# rita_milton_civ.net
KiCad netlist of a schematic drawn in EAGLE
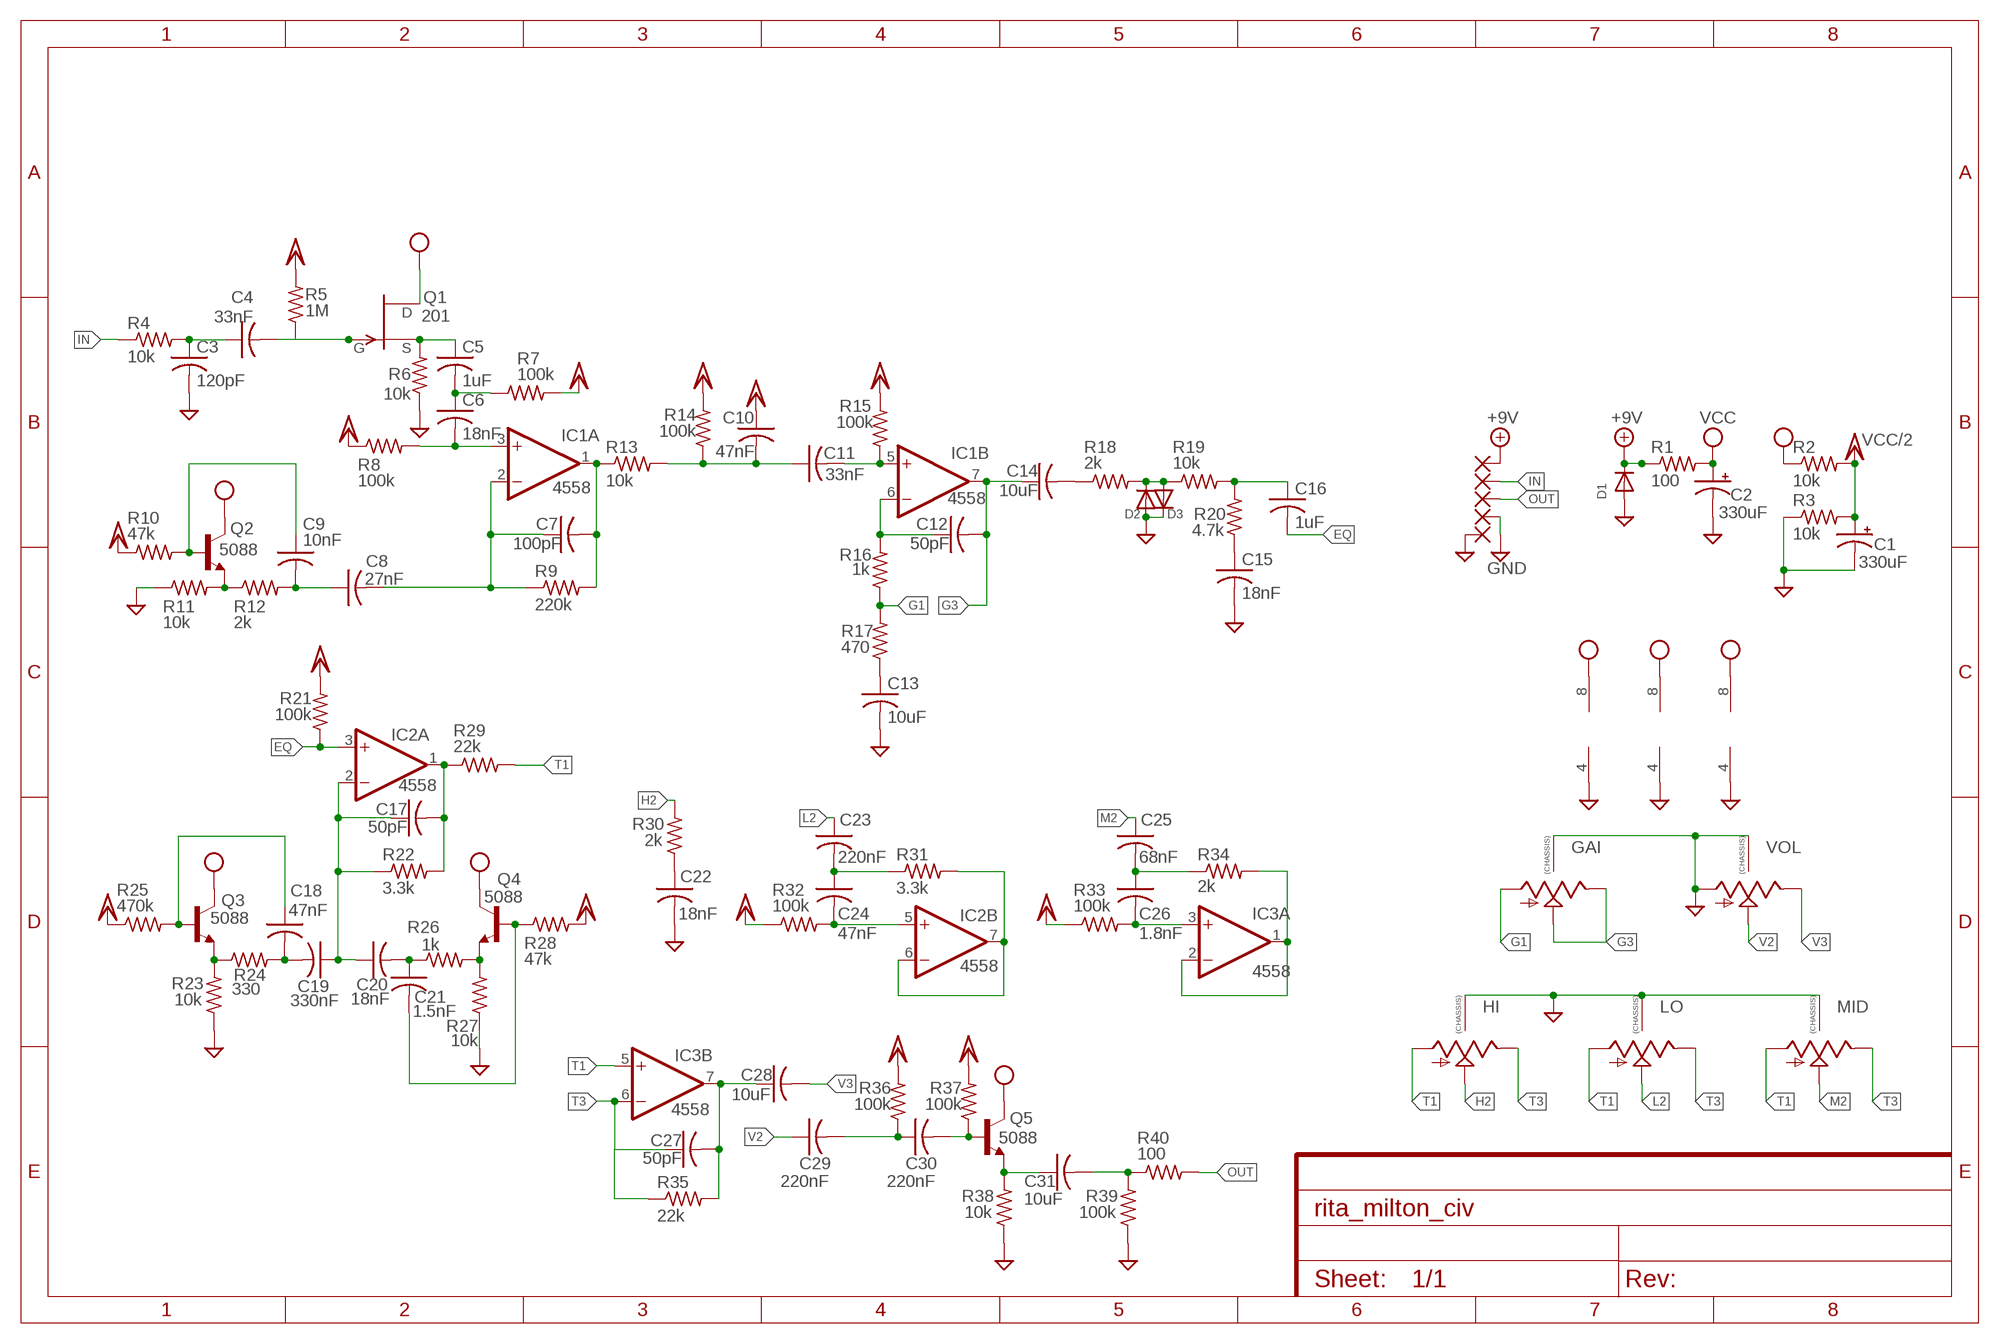
[diagram p0: schematic, sheet 1]

(export (version "E")
  (design (tool "Eeschema 10.0.6"))
  (components
    (comp (ref "C1")
      (value "330uF")
      (footprint "eagle-import:080_035")
      (libsource (lib "eagle-import") (part "0801"))
    )
    (comp (ref "C2")
      (value "330uF")
      (footprint "eagle-import:080_035")
      (libsource (lib "eagle-import") (part "0801"))
    )
    (comp (ref "C3")
      (value "120pF")
      (footprint "eagle-import:C0603")
      (libsource (lib "eagle-import") (part "adafruit_420_C-USC0603"))
    )
    (comp (ref "C4")
      (value "33nF")
      (footprint "eagle-import:C0603")
      (libsource (lib "eagle-import") (part "adafruit_420_C-USC0603"))
    )
    (comp (ref "C5")
      (value "1uF")
      (footprint "eagle-import:C0805")
      (libsource (lib "eagle-import") (part "adafruit_420_C-USC0805"))
    )
    (comp (ref "C6")
      (value "18nF")
      (footprint "eagle-import:C0603")
      (libsource (lib "eagle-import") (part "adafruit_420_C-USC0603"))
    )
    (comp (ref "C7")
      (value "100pF")
      (footprint "eagle-import:C0603")
      (libsource (lib "eagle-import") (part "adafruit_420_C-USC0603"))
    )
    (comp (ref "C8")
      (value "27nF")
      (footprint "eagle-import:C0603")
      (libsource (lib "eagle-import") (part "adafruit_420_C-USC0603"))
    )
    (comp (ref "C9")
      (value "10nF")
      (footprint "eagle-import:C0603")
      (libsource (lib "eagle-import") (part "adafruit_420_C-USC0603"))
    )
    (comp (ref "C10")
      (value "47nF")
      (footprint "eagle-import:C0603")
      (libsource (lib "eagle-import") (part "adafruit_420_C-USC0603"))
    )
    (comp (ref "C11")
      (value "33nF")
      (footprint "eagle-import:C0603")
      (libsource (lib "eagle-import") (part "adafruit_420_C-USC0603"))
    )
    (comp (ref "C12")
      (value "50pF")
      (footprint "eagle-import:C0603")
      (libsource (lib "eagle-import") (part "adafruit_420_C-USC0603"))
    )
    (comp (ref "C13")
      (value "10uF")
      (footprint "eagle-import:C1206")
      (libsource (lib "eagle-import") (part "C-USC1206"))
    )
    (comp (ref "C14")
      (value "10uF")
      (footprint "eagle-import:C1206")
      (libsource (lib "eagle-import") (part "C-USC1206"))
    )
    (comp (ref "C15")
      (value "18nF")
      (footprint "eagle-import:C0603")
      (libsource (lib "eagle-import") (part "adafruit_420_C-USC0603"))
    )
    (comp (ref "C16")
      (value "1uF")
      (footprint "eagle-import:C0805")
      (libsource (lib "eagle-import") (part "adafruit_420_C-USC0805"))
    )
    (comp (ref "C17")
      (value "50pF")
      (footprint "eagle-import:C0603")
      (libsource (lib "eagle-import") (part "adafruit_420_C-USC0603"))
    )
    (comp (ref "C18")
      (value "47nF")
      (footprint "eagle-import:C0603")
      (libsource (lib "eagle-import") (part "adafruit_420_C-USC0603"))
    )
    (comp (ref "C19")
      (value "330nF")
      (footprint "eagle-import:C0603")
      (libsource (lib "eagle-import") (part "adafruit_420_C-USC0603"))
    )
    (comp (ref "C20")
      (value "18nF")
      (footprint "eagle-import:C0603")
      (libsource (lib "eagle-import") (part "adafruit_420_C-USC0603"))
    )
    (comp (ref "C21")
      (value "1.5nF")
      (footprint "eagle-import:C0603")
      (libsource (lib "eagle-import") (part "adafruit_420_C-USC0603"))
    )
    (comp (ref "C22")
      (value "18nF")
      (footprint "eagle-import:C0603")
      (libsource (lib "eagle-import") (part "adafruit_420_C-USC0603"))
    )
    (comp (ref "C23")
      (value "220nF")
      (footprint "eagle-import:C0603")
      (libsource (lib "eagle-import") (part "adafruit_420_C-USC0603"))
    )
    (comp (ref "C24")
      (value "47nF")
      (footprint "eagle-import:C0603")
      (libsource (lib "eagle-import") (part "adafruit_420_C-USC0603"))
    )
    (comp (ref "C25")
      (value "68nF")
      (footprint "eagle-import:C0603")
      (libsource (lib "eagle-import") (part "adafruit_420_C-USC0603"))
    )
    (comp (ref "C26")
      (value "1.8nF")
      (footprint "eagle-import:C0603")
      (libsource (lib "eagle-import") (part "adafruit_420_C-USC0603"))
    )
    (comp (ref "C27")
      (value "50pF")
      (footprint "eagle-import:C0603")
      (libsource (lib "eagle-import") (part "adafruit_420_C-USC0603"))
    )
    (comp (ref "C28")
      (value "10uF")
      (footprint "eagle-import:C1206")
      (libsource (lib "eagle-import") (part "C-USC1206"))
    )
    (comp (ref "C29")
      (value "220nF")
      (footprint "eagle-import:C0603")
      (libsource (lib "eagle-import") (part "adafruit_420_C-USC0603"))
    )
    (comp (ref "C30")
      (value "220nF")
      (footprint "eagle-import:C0603")
      (libsource (lib "eagle-import") (part "adafruit_420_C-USC0603"))
    )
    (comp (ref "C31")
      (value "10uF")
      (footprint "eagle-import:C1206")
      (libsource (lib "eagle-import") (part "C-USC1206"))
    )
    (comp (ref "D1")
      (value "DIODESOD-123")
      (footprint "eagle-import:SOD-123")
      (libsource (lib "eagle-import") (part "DIODESOD-123"))
    )
    (comp (ref "D2")
      (value "DIODESOD-123")
      (footprint "eagle-import:SOD-123")
      (libsource (lib "eagle-import") (part "DIODESOD-123"))
    )
    (comp (ref "D3")
      (value "DIODESOD-123")
      (footprint "eagle-import:SOD-123")
      (libsource (lib "eagle-import") (part "DIODESOD-123"))
    )
    (comp (ref "GAI")
      (value "9MM_SNAP-IN_POT_CHASSIS")
      (footprint "eagle-import:9MM_SNAP-IN_POT")
      (libsource (lib "eagle-import") (part "9MM_SNAP-IN_POT_CHASSIS"))
    )
    (comp (ref "HI")
      (value "9MM_SNAP-IN_POT_CHASSIS")
      (footprint "eagle-import:9MM_SNAP-IN_POT")
      (libsource (lib "eagle-import") (part "9MM_SNAP-IN_POT_CHASSIS"))
    )
    (comp (ref "IC1")
      (value "4558")
      (footprint "eagle-import:SO08")
      (libsource (lib "eagle-import") (part "4558DLM"))
    )
    (comp (ref "IC2")
      (value "4558")
      (footprint "eagle-import:SO08")
      (libsource (lib "eagle-import") (part "4558DLM"))
    )
    (comp (ref "IC3")
      (value "4558")
      (footprint "eagle-import:SO08")
      (libsource (lib "eagle-import") (part "4558DLM"))
    )
    (comp (ref "LO")
      (value "9MM_SNAP-IN_POT_CHASSIS")
      (footprint "eagle-import:9MM_SNAP-IN_POT")
      (libsource (lib "eagle-import") (part "9MM_SNAP-IN_POT_CHASSIS"))
    )
    (comp (ref "MID")
      (value "9MM_SNAP-IN_POT_CHASSIS")
      (footprint "eagle-import:9MM_SNAP-IN_POT")
      (libsource (lib "eagle-import") (part "9MM_SNAP-IN_POT_CHASSIS"))
    )
    (comp (ref "PAD1")
      (value "1,6/0,8")
      (footprint "eagle-import:1,6_0,8")
      (libsource (lib "eagle-import") (part "1,6/0,8"))
    )
    (comp (ref "PAD2")
      (value "1,6/0,8")
      (footprint "eagle-import:1,6_0,8")
      (libsource (lib "eagle-import") (part "1,6/0,8"))
    )
    (comp (ref "PAD3")
      (value "1,6/0,8")
      (footprint "eagle-import:1,6_0,8")
      (libsource (lib "eagle-import") (part "1,6/0,8"))
    )
    (comp (ref "PAD4")
      (value "1,6/0,8")
      (footprint "eagle-import:1,6_0,8")
      (libsource (lib "eagle-import") (part "1,6/0,8"))
    )
    (comp (ref "PAD5")
      (value "1,6/0,8")
      (footprint "eagle-import:1,6_0,8")
      (libsource (lib "eagle-import") (part "1,6/0,8"))
    )
    (comp (ref "Q1")
      (value "201")
      (footprint "eagle-import:SOT23")
      (libsource (lib "eagle-import") (part "?20SST1"))
    )
    (comp (ref "Q2")
      (value "5088")
      (footprint "eagle-import:SOT23")
      (libsource (lib "eagle-import") (part "TRANSISTOR_NPNMMBT5088"))
    )
    (comp (ref "Q3")
      (value "5088")
      (footprint "eagle-import:SOT23")
      (libsource (lib "eagle-import") (part "TRANSISTOR_NPNMMBT5088"))
    )
    (comp (ref "Q4")
      (value "5088")
      (footprint "eagle-import:SOT23")
      (libsource (lib "eagle-import") (part "TRANSISTOR_NPNMMBT5088"))
    )
    (comp (ref "Q5")
      (value "5088")
      (footprint "eagle-import:SOT23")
      (libsource (lib "eagle-import") (part "TRANSISTOR_NPNMMBT5088"))
    )
    (comp (ref "R1")
      (value "100")
      (footprint "eagle-import:R0805")
      (libsource (lib "eagle-import") (part "R-US_R0805"))
    )
    (comp (ref "R2")
      (value "10k")
      (footprint "eagle-import:R0603")
      (libsource (lib "eagle-import") (part "R-US_R0603"))
    )
    (comp (ref "R3")
      (value "10k")
      (footprint "eagle-import:R0603")
      (libsource (lib "eagle-import") (part "R-US_R0603"))
    )
    (comp (ref "R4")
      (value "10k")
      (footprint "eagle-import:R0603")
      (libsource (lib "eagle-import") (part "adafruit_420_R-US_R0603"))
    )
    (comp (ref "R5")
      (value "1M")
      (footprint "eagle-import:R0603")
      (libsource (lib "eagle-import") (part "adafruit_420_R-US_R0603"))
    )
    (comp (ref "R6")
      (value "10k")
      (footprint "eagle-import:R0603")
      (libsource (lib "eagle-import") (part "adafruit_420_R-US_R0603"))
    )
    (comp (ref "R7")
      (value "100k")
      (footprint "eagle-import:R0603")
      (libsource (lib "eagle-import") (part "adafruit_420_R-US_R0603"))
    )
    (comp (ref "R8")
      (value "100k")
      (footprint "eagle-import:R0603")
      (libsource (lib "eagle-import") (part "adafruit_420_R-US_R0603"))
    )
    (comp (ref "R9")
      (value "220k")
      (footprint "eagle-import:R0603")
      (libsource (lib "eagle-import") (part "adafruit_420_R-US_R0603"))
    )
    (comp (ref "R10")
      (value "47k")
      (footprint "eagle-import:R0603")
      (libsource (lib "eagle-import") (part "adafruit_420_R-US_R0603"))
    )
    (comp (ref "R11")
      (value "10k")
      (footprint "eagle-import:R0603")
      (libsource (lib "eagle-import") (part "adafruit_420_R-US_R0603"))
    )
    (comp (ref "R12")
      (value "2k")
      (footprint "eagle-import:R0603")
      (libsource (lib "eagle-import") (part "adafruit_420_R-US_R0603"))
    )
    (comp (ref "R13")
      (value "10k")
      (footprint "eagle-import:R0603")
      (libsource (lib "eagle-import") (part "adafruit_420_R-US_R0603"))
    )
    (comp (ref "R14")
      (value "100k")
      (footprint "eagle-import:R0603")
      (libsource (lib "eagle-import") (part "adafruit_420_R-US_R0603"))
    )
    (comp (ref "R15")
      (value "100k")
      (footprint "eagle-import:R0603")
      (libsource (lib "eagle-import") (part "adafruit_420_R-US_R0603"))
    )
    (comp (ref "R16")
      (value "1k")
      (footprint "eagle-import:R0603")
      (libsource (lib "eagle-import") (part "adafruit_420_R-US_R0603"))
    )
    (comp (ref "R17")
      (value "470")
      (footprint "eagle-import:R0603")
      (libsource (lib "eagle-import") (part "adafruit_420_R-US_R0603"))
    )
    (comp (ref "R18")
      (value "2k")
      (footprint "eagle-import:R0603")
      (libsource (lib "eagle-import") (part "adafruit_420_R-US_R0603"))
    )
    (comp (ref "R19")
      (value "10k")
      (footprint "eagle-import:R0603")
      (libsource (lib "eagle-import") (part "adafruit_420_R-US_R0603"))
    )
    (comp (ref "R20")
      (value "4.7k")
      (footprint "eagle-import:R0603")
      (libsource (lib "eagle-import") (part "adafruit_420_R-US_R0603"))
    )
    (comp (ref "R21")
      (value "100k")
      (footprint "eagle-import:R0603")
      (libsource (lib "eagle-import") (part "adafruit_420_R-US_R0603"))
    )
    (comp (ref "R22")
      (value "3.3k")
      (footprint "eagle-import:R0603")
      (libsource (lib "eagle-import") (part "adafruit_420_R-US_R0603"))
    )
    (comp (ref "R23")
      (value "10k")
      (footprint "eagle-import:R0603")
      (libsource (lib "eagle-import") (part "adafruit_420_R-US_R0603"))
    )
    (comp (ref "R24")
      (value "330")
      (footprint "eagle-import:R0603")
      (libsource (lib "eagle-import") (part "adafruit_420_R-US_R0603"))
    )
    (comp (ref "R25")
      (value "470k")
      (footprint "eagle-import:R0603")
      (libsource (lib "eagle-import") (part "adafruit_420_R-US_R0603"))
    )
    (comp (ref "R26")
      (value "1k")
      (footprint "eagle-import:R0603")
      (libsource (lib "eagle-import") (part "adafruit_420_R-US_R0603"))
    )
    (comp (ref "R27")
      (value "10k")
      (footprint "eagle-import:R0603")
      (libsource (lib "eagle-import") (part "adafruit_420_R-US_R0603"))
    )
    (comp (ref "R28")
      (value "47k")
      (footprint "eagle-import:R0603")
      (libsource (lib "eagle-import") (part "adafruit_420_R-US_R0603"))
    )
    (comp (ref "R29")
      (value "22k")
      (footprint "eagle-import:R0603")
      (libsource (lib "eagle-import") (part "adafruit_420_R-US_R0603"))
    )
    (comp (ref "R30")
      (value "2k")
      (footprint "eagle-import:R0603")
      (libsource (lib "eagle-import") (part "adafruit_420_R-US_R0603"))
    )
    (comp (ref "R31")
      (value "3.3k")
      (footprint "eagle-import:R0603")
      (libsource (lib "eagle-import") (part "adafruit_420_R-US_R0603"))
    )
    (comp (ref "R32")
      (value "100k")
      (footprint "eagle-import:R0603")
      (libsource (lib "eagle-import") (part "adafruit_420_R-US_R0603"))
    )
    (comp (ref "R33")
      (value "100k")
      (footprint "eagle-import:R0603")
      (libsource (lib "eagle-import") (part "adafruit_420_R-US_R0603"))
    )
    (comp (ref "R34")
      (value "2k")
      (footprint "eagle-import:R0603")
      (libsource (lib "eagle-import") (part "adafruit_420_R-US_R0603"))
    )
    (comp (ref "R35")
      (value "22k")
      (footprint "eagle-import:R0603")
      (libsource (lib "eagle-import") (part "R-US_R0603"))
    )
    (comp (ref "R36")
      (value "100k")
      (footprint "eagle-import:R0603")
      (libsource (lib "eagle-import") (part "adafruit_420_R-US_R0603"))
    )
    (comp (ref "R37")
      (value "100k")
      (footprint "eagle-import:R0603")
      (libsource (lib "eagle-import") (part "adafruit_420_R-US_R0603"))
    )
    (comp (ref "R38")
      (value "10k")
      (footprint "eagle-import:R0603")
      (libsource (lib "eagle-import") (part "adafruit_420_R-US_R0603"))
    )
    (comp (ref "R39")
      (value "100k")
      (footprint "eagle-import:R0603")
      (libsource (lib "eagle-import") (part "adafruit_420_R-US_R0603"))
    )
    (comp (ref "R40")
      (value "100")
      (footprint "eagle-import:R0603")
      (libsource (lib "eagle-import") (part "adafruit_420_R-US_R0603"))
    )
    (comp (ref "VOL")
      (value "9MM_SNAP-IN_POT_CHASSIS")
      (footprint "eagle-import:9MM_SNAP-IN_POT")
      (libsource (lib "eagle-import") (part "9MM_SNAP-IN_POT_CHASSIS"))
    )
  )
  (nets
    (net (code "1") (name "+9V") (class "Default")
      (node (ref "D1") (pin "C") (pinfunction "C_C") (pintype "passive"))
      (node (ref "PAD1") (pin "1") (pinfunction "P_1") (pintype "passive"))
      (node (ref "R1") (pin "1") (pinfunction "1_1") (pintype "passive"))
    )
    (net (code "2") (name "EQ") (class "Default")
      (node (ref "C16") (pin "2") (pinfunction "2_2") (pintype "passive"))
      (node (ref "IC2") (pin "3") (pinfunction "+IN_3") (pintype "input"))
      (node (ref "R21") (pin "1") (pinfunction "1_1") (pintype "passive"))
    )
    (net (code "3") (name "G1") (class "Default")
      (node (ref "GAI") (pin "1") (pinfunction "A_1") (pintype "passive"))
      (node (ref "R16") (pin "1") (pinfunction "1_1") (pintype "passive"))
      (node (ref "R17") (pin "2") (pinfunction "2_2") (pintype "passive"))
    )
    (net (code "4") (name "G3") (class "Default")
      (node (ref "C12") (pin "2") (pinfunction "2_2") (pintype "passive"))
      (node (ref "C14") (pin "1") (pinfunction "1_1") (pintype "passive"))
      (node (ref "GAI") (pin "2") (pinfunction "S_2") (pintype "passive"))
      (node (ref "GAI") (pin "3") (pinfunction "E_3") (pintype "passive"))
      (node (ref "IC1") (pin "7") (pinfunction "OUT_7") (pintype "output"))
    )
    (net (code "5") (name "GND") (class "Default")
      (node (ref "C1") (pin "-") (pinfunction "-_-") (pintype "passive"))
      (node (ref "C13") (pin "2") (pinfunction "2_2") (pintype "passive"))
      (node (ref "C15") (pin "2") (pinfunction "2_2") (pintype "passive"))
      (node (ref "C2") (pin "-") (pinfunction "-_-") (pintype "passive"))
      (node (ref "C22") (pin "2") (pinfunction "2_2") (pintype "passive"))
      (node (ref "C3") (pin "2") (pinfunction "2_2") (pintype "passive"))
      (node (ref "D1") (pin "A") (pinfunction "A_A") (pintype "passive"))
      (node (ref "D2") (pin "A") (pinfunction "A_A") (pintype "passive"))
      (node (ref "D3") (pin "C") (pinfunction "C_C") (pintype "passive"))
      (node (ref "GAI") (pin "CHASSIS1") (pinfunction "P$1_CHASSIS1") (pintype "passive"))
      (node (ref "GAI") (pin "CHASSIS2") (pinfunction "P$1_CHASSIS2") (pintype "passive"))
      (node (ref "HI") (pin "CHASSIS1") (pinfunction "P$1_CHASSIS1") (pintype "passive"))
      (node (ref "HI") (pin "CHASSIS2") (pinfunction "P$1_CHASSIS2") (pintype "passive"))
      (node (ref "IC1") (pin "4") (pinfunction "V-_4") (pintype "power_in"))
      (node (ref "IC2") (pin "4") (pinfunction "V-_4") (pintype "power_in"))
      (node (ref "IC3") (pin "4") (pinfunction "V-_4") (pintype "power_in"))
      (node (ref "LO") (pin "CHASSIS1") (pinfunction "P$1_CHASSIS1") (pintype "passive"))
      (node (ref "LO") (pin "CHASSIS2") (pinfunction "P$1_CHASSIS2") (pintype "passive"))
      (node (ref "MID") (pin "CHASSIS1") (pinfunction "P$1_CHASSIS1") (pintype "passive"))
      (node (ref "MID") (pin "CHASSIS2") (pinfunction "P$1_CHASSIS2") (pintype "passive"))
      (node (ref "PAD4") (pin "1") (pinfunction "P_1") (pintype "passive"))
      (node (ref "PAD5") (pin "1") (pinfunction "P_1") (pintype "passive"))
      (node (ref "R11") (pin "1") (pinfunction "1_1") (pintype "passive"))
      (node (ref "R23") (pin "1") (pinfunction "1_1") (pintype "passive"))
      (node (ref "R27") (pin "1") (pinfunction "1_1") (pintype "passive"))
      (node (ref "R3") (pin "1") (pinfunction "1_1") (pintype "passive"))
      (node (ref "R38") (pin "1") (pinfunction "1_1") (pintype "passive"))
      (node (ref "R39") (pin "1") (pinfunction "1_1") (pintype "passive"))
      (node (ref "R6") (pin "1") (pinfunction "1_1") (pintype "passive"))
      (node (ref "VOL") (pin "1") (pinfunction "A_1") (pintype "passive"))
      (node (ref "VOL") (pin "CHASSIS1") (pinfunction "P$1_CHASSIS1") (pintype "passive"))
      (node (ref "VOL") (pin "CHASSIS2") (pinfunction "P$1_CHASSIS2") (pintype "passive"))
    )
    (net (code "6") (name "H2") (class "Default")
      (node (ref "HI") (pin "2") (pinfunction "S_2") (pintype "passive"))
      (node (ref "R30") (pin "2") (pinfunction "2_2") (pintype "passive"))
    )
    (net (code "7") (name "IN") (class "Default")
      (node (ref "PAD2") (pin "1") (pinfunction "P_1") (pintype "passive"))
      (node (ref "R4") (pin "1") (pinfunction "1_1") (pintype "passive"))
    )
    (net (code "8") (name "L2") (class "Default")
      (node (ref "C23") (pin "1") (pinfunction "1_1") (pintype "passive"))
      (node (ref "LO") (pin "2") (pinfunction "S_2") (pintype "passive"))
    )
    (net (code "9") (name "M2") (class "Default")
      (node (ref "C25") (pin "1") (pinfunction "1_1") (pintype "passive"))
      (node (ref "MID") (pin "2") (pinfunction "S_2") (pintype "passive"))
    )
    (net (code "10") (name "Net-(C3-Pad1)") (class "Default")
      (node (ref "C3") (pin "1") (pinfunction "1_1") (pintype "passive"))
      (node (ref "C4") (pin "1") (pinfunction "1_1") (pintype "passive"))
      (node (ref "R4") (pin "2") (pinfunction "2_2") (pintype "passive"))
    )
    (net (code "11") (name "Net-(C5-Pad2)") (class "Default")
      (node (ref "C5") (pin "2") (pinfunction "2_2") (pintype "passive"))
      (node (ref "C6") (pin "1") (pinfunction "1_1") (pintype "passive"))
      (node (ref "R7") (pin "1") (pinfunction "1_1") (pintype "passive"))
    )
    (net (code "12") (name "Net-(C8-Pad1)") (class "Default")
      (node (ref "C8") (pin "1") (pinfunction "1_1") (pintype "passive"))
      (node (ref "C9") (pin "2") (pinfunction "2_2") (pintype "passive"))
      (node (ref "R12") (pin "2") (pinfunction "2_2") (pintype "passive"))
    )
    (net (code "13") (name "Net-(C10-Pad2)") (class "Default")
      (node (ref "C10") (pin "2") (pinfunction "2_2") (pintype "passive"))
      (node (ref "C11") (pin "1") (pinfunction "1_1") (pintype "passive"))
      (node (ref "R13") (pin "2") (pinfunction "2_2") (pintype "passive"))
      (node (ref "R14") (pin "1") (pinfunction "1_1") (pintype "passive"))
    )
    (net (code "14") (name "Net-(C13-Pad1)") (class "Default")
      (node (ref "C13") (pin "1") (pinfunction "1_1") (pintype "passive"))
      (node (ref "R17") (pin "1") (pinfunction "1_1") (pintype "passive"))
    )
    (net (code "15") (name "Net-(C14-Pad2)") (class "Default")
      (node (ref "C14") (pin "2") (pinfunction "2_2") (pintype "passive"))
      (node (ref "R18") (pin "1") (pinfunction "1_1") (pintype "passive"))
    )
    (net (code "16") (name "Net-(C15-Pad1)") (class "Default")
      (node (ref "C15") (pin "1") (pinfunction "1_1") (pintype "passive"))
      (node (ref "R20") (pin "1") (pinfunction "1_1") (pintype "passive"))
    )
    (net (code "17") (name "Net-(C16-Pad1)") (class "Default")
      (node (ref "C16") (pin "1") (pinfunction "1_1") (pintype "passive"))
      (node (ref "R19") (pin "2") (pinfunction "2_2") (pintype "passive"))
      (node (ref "R20") (pin "2") (pinfunction "2_2") (pintype "passive"))
    )
    (net (code "18") (name "Net-(C18-Pad2)") (class "Default")
      (node (ref "C18") (pin "2") (pinfunction "2_2") (pintype "passive"))
      (node (ref "C19") (pin "2") (pinfunction "2_2") (pintype "passive"))
      (node (ref "R24") (pin "2") (pinfunction "2_2") (pintype "passive"))
    )
    (net (code "19") (name "Net-(C20-Pad2)") (class "Default")
      (node (ref "C20") (pin "2") (pinfunction "2_2") (pintype "passive"))
      (node (ref "C21") (pin "1") (pinfunction "1_1") (pintype "passive"))
      (node (ref "R26") (pin "1") (pinfunction "1_1") (pintype "passive"))
    )
    (net (code "20") (name "Net-(C22-Pad1)") (class "Default")
      (node (ref "C22") (pin "1") (pinfunction "1_1") (pintype "passive"))
      (node (ref "R30") (pin "1") (pinfunction "1_1") (pintype "passive"))
    )
    (net (code "21") (name "Net-(C23-Pad2)") (class "Default")
      (node (ref "C23") (pin "2") (pinfunction "2_2") (pintype "passive"))
      (node (ref "C24") (pin "1") (pinfunction "1_1") (pintype "passive"))
      (node (ref "R31") (pin "1") (pinfunction "1_1") (pintype "passive"))
    )
    (net (code "22") (name "Net-(C25-Pad2)") (class "Default")
      (node (ref "C25") (pin "2") (pinfunction "2_2") (pintype "passive"))
      (node (ref "C26") (pin "1") (pinfunction "1_1") (pintype "passive"))
      (node (ref "R34") (pin "1") (pinfunction "1_1") (pintype "passive"))
    )
    (net (code "23") (name "Net-(C29-Pad2)") (class "Default")
      (node (ref "C29") (pin "2") (pinfunction "2_2") (pintype "passive"))
      (node (ref "C30") (pin "1") (pinfunction "1_1") (pintype "passive"))
      (node (ref "R36") (pin "1") (pinfunction "1_1") (pintype "passive"))
    )
    (net (code "24") (name "Net-(C31-Pad2)") (class "Default")
      (node (ref "C31") (pin "2") (pinfunction "2_2") (pintype "passive"))
      (node (ref "R39") (pin "2") (pinfunction "2_2") (pintype "passive"))
      (node (ref "R40") (pin "1") (pinfunction "1_1") (pintype "passive"))
    )
    (net (code "25") (name "Net-(D2-PadC)") (class "Default")
      (node (ref "D2") (pin "C") (pinfunction "C_C") (pintype "passive"))
      (node (ref "D3") (pin "A") (pinfunction "A_A") (pintype "passive"))
      (node (ref "R18") (pin "2") (pinfunction "2_2") (pintype "passive"))
      (node (ref "R19") (pin "1") (pinfunction "1_1") (pintype "passive"))
    )
    (net (code "26") (name "Net-(IC1A-+IN)") (class "Default")
      (node (ref "C6") (pin "2") (pinfunction "2_2") (pintype "passive"))
      (node (ref "IC1") (pin "3") (pinfunction "+IN_3") (pintype "input"))
      (node (ref "R8") (pin "2") (pinfunction "2_2") (pintype "passive"))
    )
    (net (code "27") (name "Net-(IC1A--IN)") (class "Default")
      (node (ref "C7") (pin "1") (pinfunction "1_1") (pintype "passive"))
      (node (ref "C8") (pin "2") (pinfunction "2_2") (pintype "passive"))
      (node (ref "IC1") (pin "2") (pinfunction "-IN_2") (pintype "input"))
      (node (ref "R9") (pin "1") (pinfunction "1_1") (pintype "passive"))
    )
    (net (code "28") (name "Net-(IC1A-OUT)") (class "Default")
      (node (ref "C7") (pin "2") (pinfunction "2_2") (pintype "passive"))
      (node (ref "IC1") (pin "1") (pinfunction "OUT_1") (pintype "output"))
      (node (ref "R13") (pin "1") (pinfunction "1_1") (pintype "passive"))
      (node (ref "R9") (pin "2") (pinfunction "2_2") (pintype "passive"))
    )
    (net (code "29") (name "Net-(IC1B-+IN)") (class "Default")
      (node (ref "C11") (pin "2") (pinfunction "2_2") (pintype "passive"))
      (node (ref "IC1") (pin "5") (pinfunction "+IN_5") (pintype "input"))
      (node (ref "R15") (pin "1") (pinfunction "1_1") (pintype "passive"))
    )
    (net (code "30") (name "Net-(IC1B--IN)") (class "Default")
      (node (ref "C12") (pin "1") (pinfunction "1_1") (pintype "passive"))
      (node (ref "IC1") (pin "6") (pinfunction "-IN_6") (pintype "input"))
      (node (ref "R16") (pin "2") (pinfunction "2_2") (pintype "passive"))
    )
    (net (code "31") (name "Net-(IC2A--IN)") (class "Default")
      (node (ref "C17") (pin "1") (pinfunction "1_1") (pintype "passive"))
      (node (ref "C19") (pin "1") (pinfunction "1_1") (pintype "passive"))
      (node (ref "C20") (pin "1") (pinfunction "1_1") (pintype "passive"))
      (node (ref "IC2") (pin "2") (pinfunction "-IN_2") (pintype "input"))
      (node (ref "R22") (pin "1") (pinfunction "1_1") (pintype "passive"))
    )
    (net (code "32") (name "Net-(IC2A-OUT)") (class "Default")
      (node (ref "C17") (pin "2") (pinfunction "2_2") (pintype "passive"))
      (node (ref "IC2") (pin "1") (pinfunction "OUT_1") (pintype "output"))
      (node (ref "R22") (pin "2") (pinfunction "2_2") (pintype "passive"))
      (node (ref "R29") (pin "1") (pinfunction "1_1") (pintype "passive"))
    )
    (net (code "33") (name "Net-(IC2B-+IN)") (class "Default")
      (node (ref "C24") (pin "2") (pinfunction "2_2") (pintype "passive"))
      (node (ref "IC2") (pin "5") (pinfunction "+IN_5") (pintype "input"))
      (node (ref "R32") (pin "2") (pinfunction "2_2") (pintype "passive"))
    )
    (net (code "34") (name "Net-(IC2B--IN)") (class "Default")
      (node (ref "IC2") (pin "6") (pinfunction "-IN_6") (pintype "input"))
      (node (ref "IC2") (pin "7") (pinfunction "OUT_7") (pintype "output"))
      (node (ref "R31") (pin "2") (pinfunction "2_2") (pintype "passive"))
    )
    (net (code "35") (name "Net-(IC3A-+IN)") (class "Default")
      (node (ref "C26") (pin "2") (pinfunction "2_2") (pintype "passive"))
      (node (ref "IC3") (pin "3") (pinfunction "+IN_3") (pintype "input"))
      (node (ref "R33") (pin "2") (pinfunction "2_2") (pintype "passive"))
    )
    (net (code "36") (name "Net-(IC3A--IN)") (class "Default")
      (node (ref "IC3") (pin "1") (pinfunction "OUT_1") (pintype "output"))
      (node (ref "IC3") (pin "2") (pinfunction "-IN_2") (pintype "input"))
      (node (ref "R34") (pin "2") (pinfunction "2_2") (pintype "passive"))
    )
    (net (code "37") (name "Net-(IC3B-OUT)") (class "Default")
      (node (ref "C27") (pin "2") (pinfunction "2_2") (pintype "passive"))
      (node (ref "C28") (pin "1") (pinfunction "1_1") (pintype "passive"))
      (node (ref "IC3") (pin "7") (pinfunction "OUT_7") (pintype "output"))
      (node (ref "R35") (pin "2") (pinfunction "2_2") (pintype "passive"))
    )
    (net (code "38") (name "Net-(Q1-G)") (class "Default")
      (node (ref "C4") (pin "2") (pinfunction "2_2") (pintype "passive"))
      (node (ref "Q1") (pin "3") (pinfunction "G_3") (pintype "passive"))
      (node (ref "R5") (pin "1") (pinfunction "1_1") (pintype "passive"))
    )
    (net (code "39") (name "Net-(Q1-S)") (class "Default")
      (node (ref "C5") (pin "1") (pinfunction "1_1") (pintype "passive"))
      (node (ref "Q1") (pin "2") (pinfunction "S_2") (pintype "passive"))
      (node (ref "R6") (pin "2") (pinfunction "2_2") (pintype "passive"))
    )
    (net (code "40") (name "Net-(Q2-B)") (class "Default")
      (node (ref "C9") (pin "1") (pinfunction "1_1") (pintype "passive"))
      (node (ref "Q2") (pin "1") (pinfunction "B_1") (pintype "passive"))
      (node (ref "R10") (pin "2") (pinfunction "2_2") (pintype "passive"))
    )
    (net (code "41") (name "Net-(Q2-E)") (class "Default")
      (node (ref "Q2") (pin "2") (pinfunction "E_2") (pintype "passive"))
      (node (ref "R11") (pin "2") (pinfunction "2_2") (pintype "passive"))
      (node (ref "R12") (pin "1") (pinfunction "1_1") (pintype "passive"))
    )
    (net (code "42") (name "Net-(Q3-B)") (class "Default")
      (node (ref "C18") (pin "1") (pinfunction "1_1") (pintype "passive"))
      (node (ref "Q3") (pin "1") (pinfunction "B_1") (pintype "passive"))
      (node (ref "R25") (pin "2") (pinfunction "2_2") (pintype "passive"))
    )
    (net (code "43") (name "Net-(Q3-E)") (class "Default")
      (node (ref "Q3") (pin "2") (pinfunction "E_2") (pintype "passive"))
      (node (ref "R23") (pin "2") (pinfunction "2_2") (pintype "passive"))
      (node (ref "R24") (pin "1") (pinfunction "1_1") (pintype "passive"))
    )
    (net (code "44") (name "Net-(Q4-B)") (class "Default")
      (node (ref "C21") (pin "2") (pinfunction "2_2") (pintype "passive"))
      (node (ref "Q4") (pin "1") (pinfunction "B_1") (pintype "passive"))
      (node (ref "R28") (pin "1") (pinfunction "1_1") (pintype "passive"))
    )
    (net (code "45") (name "Net-(Q4-E)") (class "Default")
      (node (ref "Q4") (pin "2") (pinfunction "E_2") (pintype "passive"))
      (node (ref "R26") (pin "2") (pinfunction "2_2") (pintype "passive"))
      (node (ref "R27") (pin "2") (pinfunction "2_2") (pintype "passive"))
    )
    (net (code "46") (name "Net-(Q5-B)") (class "Default")
      (node (ref "C30") (pin "2") (pinfunction "2_2") (pintype "passive"))
      (node (ref "Q5") (pin "1") (pinfunction "B_1") (pintype "passive"))
      (node (ref "R37") (pin "1") (pinfunction "1_1") (pintype "passive"))
    )
    (net (code "47") (name "Net-(Q5-E)") (class "Default")
      (node (ref "C31") (pin "1") (pinfunction "1_1") (pintype "passive"))
      (node (ref "Q5") (pin "2") (pinfunction "E_2") (pintype "passive"))
      (node (ref "R38") (pin "2") (pinfunction "2_2") (pintype "passive"))
    )
    (net (code "48") (name "OUT") (class "Default")
      (node (ref "PAD3") (pin "1") (pinfunction "P_1") (pintype "passive"))
      (node (ref "R40") (pin "2") (pinfunction "2_2") (pintype "passive"))
    )
    (net (code "49") (name "T1") (class "Default")
      (node (ref "HI") (pin "1") (pinfunction "A_1") (pintype "passive"))
      (node (ref "IC3") (pin "5") (pinfunction "+IN_5") (pintype "input"))
      (node (ref "LO") (pin "1") (pinfunction "A_1") (pintype "passive"))
      (node (ref "MID") (pin "1") (pinfunction "A_1") (pintype "passive"))
      (node (ref "R29") (pin "2") (pinfunction "2_2") (pintype "passive"))
    )
    (net (code "50") (name "T3") (class "Default")
      (node (ref "C27") (pin "1") (pinfunction "1_1") (pintype "passive"))
      (node (ref "HI") (pin "3") (pinfunction "E_3") (pintype "passive"))
      (node (ref "IC3") (pin "6") (pinfunction "-IN_6") (pintype "input"))
      (node (ref "LO") (pin "3") (pinfunction "E_3") (pintype "passive"))
      (node (ref "MID") (pin "3") (pinfunction "E_3") (pintype "passive"))
      (node (ref "R35") (pin "1") (pinfunction "1_1") (pintype "passive"))
    )
    (net (code "51") (name "V2") (class "Default")
      (node (ref "C29") (pin "1") (pinfunction "1_1") (pintype "passive"))
      (node (ref "VOL") (pin "2") (pinfunction "S_2") (pintype "passive"))
    )
    (net (code "52") (name "V3") (class "Default")
      (node (ref "C28") (pin "2") (pinfunction "2_2") (pintype "passive"))
      (node (ref "VOL") (pin "3") (pinfunction "E_3") (pintype "passive"))
    )
    (net (code "53") (name "VCC") (class "Default")
      (node (ref "C2") (pin "+") (pinfunction "+_+") (pintype "passive"))
      (node (ref "IC1") (pin "8") (pinfunction "V+_8") (pintype "power_in"))
      (node (ref "IC2") (pin "8") (pinfunction "V+_8") (pintype "power_in"))
      (node (ref "IC3") (pin "8") (pinfunction "V+_8") (pintype "power_in"))
      (node (ref "Q1") (pin "1") (pinfunction "D_1") (pintype "passive"))
      (node (ref "Q2") (pin "3") (pinfunction "C_3") (pintype "passive"))
      (node (ref "Q3") (pin "3") (pinfunction "C_3") (pintype "passive"))
      (node (ref "Q4") (pin "3") (pinfunction "C_3") (pintype "passive"))
      (node (ref "Q5") (pin "3") (pinfunction "C_3") (pintype "passive"))
      (node (ref "R1") (pin "2") (pinfunction "2_2") (pintype "passive"))
      (node (ref "R2") (pin "1") (pinfunction "1_1") (pintype "passive"))
    )
    (net (code "54") (name "VCC{slash}2") (class "Default")
      (node (ref "C1") (pin "+") (pinfunction "+_+") (pintype "passive"))
      (node (ref "C10") (pin "1") (pinfunction "1_1") (pintype "passive"))
      (node (ref "R10") (pin "1") (pinfunction "1_1") (pintype "passive"))
      (node (ref "R14") (pin "2") (pinfunction "2_2") (pintype "passive"))
      (node (ref "R15") (pin "2") (pinfunction "2_2") (pintype "passive"))
      (node (ref "R2") (pin "2") (pinfunction "2_2") (pintype "passive"))
      (node (ref "R21") (pin "2") (pinfunction "2_2") (pintype "passive"))
      (node (ref "R25") (pin "1") (pinfunction "1_1") (pintype "passive"))
      (node (ref "R28") (pin "2") (pinfunction "2_2") (pintype "passive"))
      (node (ref "R3") (pin "2") (pinfunction "2_2") (pintype "passive"))
      (node (ref "R32") (pin "1") (pinfunction "1_1") (pintype "passive"))
      (node (ref "R33") (pin "1") (pinfunction "1_1") (pintype "passive"))
      (node (ref "R36") (pin "2") (pinfunction "2_2") (pintype "passive"))
      (node (ref "R37") (pin "2") (pinfunction "2_2") (pintype "passive"))
      (node (ref "R5") (pin "2") (pinfunction "2_2") (pintype "passive"))
      (node (ref "R7") (pin "2") (pinfunction "2_2") (pintype "passive"))
      (node (ref "R8") (pin "1") (pinfunction "1_1") (pintype "passive"))
    )
  )
)
